# guitar_balanced_driver_x2.net
KiCad netlist of a schematic drawn in EAGLE
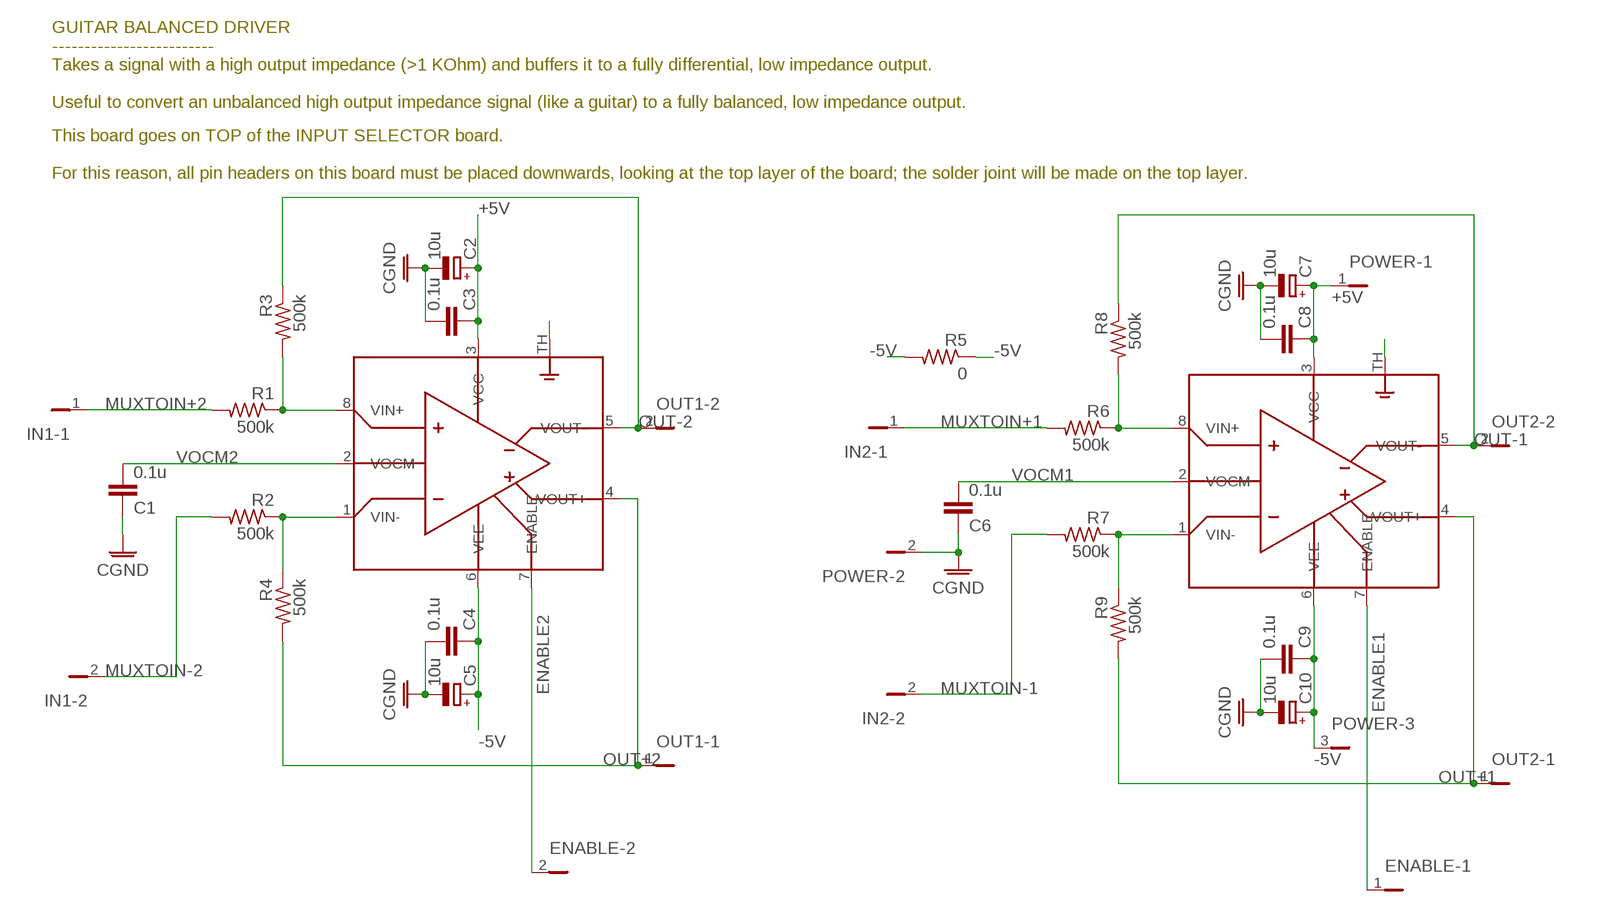
[diagram p0: schematic, sheet 1]

(export (version "E")
  (design (tool "Eeschema 10.0.6"))
  (components
    (comp (ref "C1")
      (value "0.1u")
      (footprint "eagle-import:C0603")
      (libsource (lib "eagle-import") (part "C-EUC0603"))
    )
    (comp (ref "C2")
      (value "10u")
      (footprint "eagle-import:PANASONIC_A")
      (libsource (lib "eagle-import") (part "CPOL-EUA"))
    )
    (comp (ref "C3")
      (value "0.1u")
      (footprint "eagle-import:C0603")
      (libsource (lib "eagle-import") (part "C-EUC0603"))
    )
    (comp (ref "C4")
      (value "0.1u")
      (footprint "eagle-import:C0603")
      (libsource (lib "eagle-import") (part "C-EUC0603"))
    )
    (comp (ref "C5")
      (value "10u")
      (footprint "eagle-import:PANASONIC_A")
      (libsource (lib "eagle-import") (part "CPOL-EUA"))
    )
    (comp (ref "C6")
      (value "0.1u")
      (footprint "eagle-import:C0603")
      (libsource (lib "eagle-import") (part "C-EUC0603"))
    )
    (comp (ref "C7")
      (value "10u")
      (footprint "eagle-import:PANASONIC_A")
      (libsource (lib "eagle-import") (part "CPOL-EUA"))
    )
    (comp (ref "C8")
      (value "0.1u")
      (footprint "eagle-import:C0603")
      (libsource (lib "eagle-import") (part "C-EUC0603"))
    )
    (comp (ref "C9")
      (value "0.1u")
      (footprint "eagle-import:C0603")
      (libsource (lib "eagle-import") (part "C-EUC0603"))
    )
    (comp (ref "C10")
      (value "10u")
      (footprint "eagle-import:PANASONIC_A")
      (libsource (lib "eagle-import") (part "CPOL-EUA"))
    )
    (comp (ref "ENABLE")
      (value "PINHD-1X2")
      (footprint "eagle-import:1X02")
      (libsource (lib "eagle-import") (part "PINHD-1X2"))
    )
    (comp (ref "IN1")
      (value "PINHD-1X2")
      (footprint "eagle-import:1X02")
      (libsource (lib "eagle-import") (part "PINHD-1X2"))
    )
    (comp (ref "IN2")
      (value "PINHD-1X2")
      (footprint "eagle-import:1X02")
      (libsource (lib "eagle-import") (part "PINHD-1X2"))
    )
    (comp (ref "OA1")
      (value "LME49724")
      (footprint "eagle-import:S-PDSO-G08")
      (libsource (lib "eagle-import") (part "LME49724"))
    )
    (comp (ref "OA2")
      (value "LME49724")
      (footprint "eagle-import:S-PDSO-G08")
      (libsource (lib "eagle-import") (part "LME49724"))
    )
    (comp (ref "OUT1")
      (value "PINHD-1X2")
      (footprint "eagle-import:1X02")
      (libsource (lib "eagle-import") (part "PINHD-1X2"))
    )
    (comp (ref "OUT2")
      (value "PINHD-1X2")
      (footprint "eagle-import:1X02")
      (libsource (lib "eagle-import") (part "PINHD-1X2"))
    )
    (comp (ref "POWER")
      (value "PINHD-1X3")
      (footprint "eagle-import:1X03")
      (libsource (lib "eagle-import") (part "PINHD-1X3"))
    )
    (comp (ref "R1")
      (value "500k")
      (footprint "eagle-import:R0603")
      (libsource (lib "eagle-import") (part "R-US_R0603"))
    )
    (comp (ref "R2")
      (value "500k")
      (footprint "eagle-import:R0603")
      (libsource (lib "eagle-import") (part "R-US_R0603"))
    )
    (comp (ref "R3")
      (value "500k")
      (footprint "eagle-import:R0603")
      (libsource (lib "eagle-import") (part "R-US_R0603"))
    )
    (comp (ref "R4")
      (value "500k")
      (footprint "eagle-import:R0603")
      (libsource (lib "eagle-import") (part "R-US_R0603"))
    )
    (comp (ref "R5")
      (value "0")
      (footprint "eagle-import:R0603")
      (libsource (lib "eagle-import") (part "R-US_R0603"))
    )
    (comp (ref "R6")
      (value "500k")
      (footprint "eagle-import:R0603")
      (libsource (lib "eagle-import") (part "R-US_R0603"))
    )
    (comp (ref "R7")
      (value "500k")
      (footprint "eagle-import:R0603")
      (libsource (lib "eagle-import") (part "R-US_R0603"))
    )
    (comp (ref "R8")
      (value "500k")
      (footprint "eagle-import:R0603")
      (libsource (lib "eagle-import") (part "R-US_R0603"))
    )
    (comp (ref "R9")
      (value "500k")
      (footprint "eagle-import:R0603")
      (libsource (lib "eagle-import") (part "R-US_R0603"))
    )
  )
  (nets
    (net (code "1") (name "/+5V") (class "Default")
      (node (ref "C2") (pin "+") (pinfunction "+_+") (pintype "passive"))
      (node (ref "C3") (pin "1") (pinfunction "1_1") (pintype "passive"))
      (node (ref "C7") (pin "+") (pinfunction "+_+") (pintype "passive"))
      (node (ref "C8") (pin "1") (pinfunction "1_1") (pintype "passive"))
      (node (ref "OA1") (pin "3") (pinfunction "VCC_3") (pintype "power_in"))
      (node (ref "OA2") (pin "3") (pinfunction "VCC_3") (pintype "power_in"))
      (node (ref "POWER") (pin "1") (pinfunction "S_1") (pintype "passive"))
    )
    (net (code "2") (name "/-5V") (class "Default")
      (node (ref "C10") (pin "+") (pinfunction "+_+") (pintype "passive"))
      (node (ref "C4") (pin "1") (pinfunction "1_1") (pintype "passive"))
      (node (ref "C5") (pin "+") (pinfunction "+_+") (pintype "passive"))
      (node (ref "C9") (pin "1") (pinfunction "1_1") (pintype "passive"))
      (node (ref "OA1") (pin "6") (pinfunction "VEE_6") (pintype "power_in"))
      (node (ref "OA1") (pin "TH") (pinfunction "POWERPAD_TH") (pintype "power_in"))
      (node (ref "OA2") (pin "6") (pinfunction "VEE_6") (pintype "power_in"))
      (node (ref "OA2") (pin "TH") (pinfunction "POWERPAD_TH") (pintype "power_in"))
      (node (ref "POWER") (pin "3") (pinfunction "S_3") (pintype "passive"))
      (node (ref "R5") (pin "1") (pinfunction "1_1") (pintype "passive"))
      (node (ref "R5") (pin "2") (pinfunction "2_2") (pintype "passive"))
    )
    (net (code "3") (name "/ENABLE1") (class "Default")
      (node (ref "ENABLE") (pin "1") (pinfunction "S_1") (pintype "passive"))
      (node (ref "OA2") (pin "7") (pinfunction "ENABLE_7") (pintype "input"))
    )
    (net (code "4") (name "/ENABLE2") (class "Default")
      (node (ref "ENABLE") (pin "2") (pinfunction "S_2") (pintype "passive"))
      (node (ref "OA1") (pin "7") (pinfunction "ENABLE_7") (pintype "input"))
    )
    (net (code "5") (name "/MUXTOIN+1") (class "Default")
      (node (ref "IN2") (pin "1") (pinfunction "S_1") (pintype "passive"))
      (node (ref "R6") (pin "2") (pinfunction "2_2") (pintype "passive"))
    )
    (net (code "6") (name "/MUXTOIN+2") (class "Default")
      (node (ref "IN1") (pin "1") (pinfunction "S_1") (pintype "passive"))
      (node (ref "R1") (pin "2") (pinfunction "2_2") (pintype "passive"))
    )
    (net (code "7") (name "/MUXTOIN-1") (class "Default")
      (node (ref "IN2") (pin "2") (pinfunction "S_2") (pintype "passive"))
      (node (ref "R7") (pin "2") (pinfunction "2_2") (pintype "passive"))
    )
    (net (code "8") (name "/MUXTOIN-2") (class "Default")
      (node (ref "IN1") (pin "2") (pinfunction "S_2") (pintype "passive"))
      (node (ref "R2") (pin "2") (pinfunction "2_2") (pintype "passive"))
    )
    (net (code "9") (name "/OUT+1") (class "Default")
      (node (ref "OA2") (pin "4") (pinfunction "VOUT+_4") (pintype "output"))
      (node (ref "OUT2") (pin "1") (pinfunction "S_1") (pintype "passive"))
      (node (ref "R9") (pin "2") (pinfunction "2_2") (pintype "passive"))
    )
    (net (code "10") (name "/OUT+2") (class "Default")
      (node (ref "OA1") (pin "4") (pinfunction "VOUT+_4") (pintype "output"))
      (node (ref "OUT1") (pin "1") (pinfunction "S_1") (pintype "passive"))
      (node (ref "R4") (pin "2") (pinfunction "2_2") (pintype "passive"))
    )
    (net (code "11") (name "/OUT-1") (class "Default")
      (node (ref "OA2") (pin "5") (pinfunction "VOUT-_5") (pintype "output"))
      (node (ref "OUT2") (pin "2") (pinfunction "S_2") (pintype "passive"))
      (node (ref "R8") (pin "1") (pinfunction "1_1") (pintype "passive"))
    )
    (net (code "12") (name "/OUT-2") (class "Default")
      (node (ref "OA1") (pin "5") (pinfunction "VOUT-_5") (pintype "output"))
      (node (ref "OUT1") (pin "2") (pinfunction "S_2") (pintype "passive"))
      (node (ref "R3") (pin "1") (pinfunction "1_1") (pintype "passive"))
    )
    (net (code "13") (name "/VOCM1") (class "Default")
      (node (ref "C6") (pin "2") (pinfunction "2_2") (pintype "passive"))
      (node (ref "OA2") (pin "2") (pinfunction "VOCM_2") (pintype "input"))
    )
    (net (code "14") (name "/VOCM2") (class "Default")
      (node (ref "C1") (pin "2") (pinfunction "2_2") (pintype "passive"))
      (node (ref "OA1") (pin "2") (pinfunction "VOCM_2") (pintype "input"))
    )
    (net (code "15") (name "CGND") (class "Default")
      (node (ref "C1") (pin "1") (pinfunction "1_1") (pintype "passive"))
      (node (ref "C10") (pin "-") (pinfunction "-_-") (pintype "passive"))
      (node (ref "C2") (pin "-") (pinfunction "-_-") (pintype "passive"))
      (node (ref "C3") (pin "2") (pinfunction "2_2") (pintype "passive"))
      (node (ref "C4") (pin "2") (pinfunction "2_2") (pintype "passive"))
      (node (ref "C5") (pin "-") (pinfunction "-_-") (pintype "passive"))
      (node (ref "C6") (pin "1") (pinfunction "1_1") (pintype "passive"))
      (node (ref "C7") (pin "-") (pinfunction "-_-") (pintype "passive"))
      (node (ref "C8") (pin "2") (pinfunction "2_2") (pintype "passive"))
      (node (ref "C9") (pin "2") (pinfunction "2_2") (pintype "passive"))
      (node (ref "POWER") (pin "2") (pinfunction "S_2") (pintype "passive"))
    )
    (net (code "16") (name "Net-(OA1-VIN+)") (class "Default")
      (node (ref "OA1") (pin "8") (pinfunction "VIN+_8") (pintype "input"))
      (node (ref "R1") (pin "1") (pinfunction "1_1") (pintype "passive"))
      (node (ref "R3") (pin "2") (pinfunction "2_2") (pintype "passive"))
    )
    (net (code "17") (name "Net-(OA1-VIN-)") (class "Default")
      (node (ref "OA1") (pin "1") (pinfunction "VIN-_1") (pintype "input"))
      (node (ref "R2") (pin "1") (pinfunction "1_1") (pintype "passive"))
      (node (ref "R4") (pin "1") (pinfunction "1_1") (pintype "passive"))
    )
    (net (code "18") (name "Net-(OA2-VIN+)") (class "Default")
      (node (ref "OA2") (pin "8") (pinfunction "VIN+_8") (pintype "input"))
      (node (ref "R6") (pin "1") (pinfunction "1_1") (pintype "passive"))
      (node (ref "R8") (pin "2") (pinfunction "2_2") (pintype "passive"))
    )
    (net (code "19") (name "Net-(OA2-VIN-)") (class "Default")
      (node (ref "OA2") (pin "1") (pinfunction "VIN-_1") (pintype "input"))
      (node (ref "R7") (pin "1") (pinfunction "1_1") (pintype "passive"))
      (node (ref "R9") (pin "1") (pinfunction "1_1") (pintype "passive"))
    )
  )
)
